# SCH_IMU_Tester_2024-10-07.net
KiCad netlist of a schematic drawn in EasyEDA
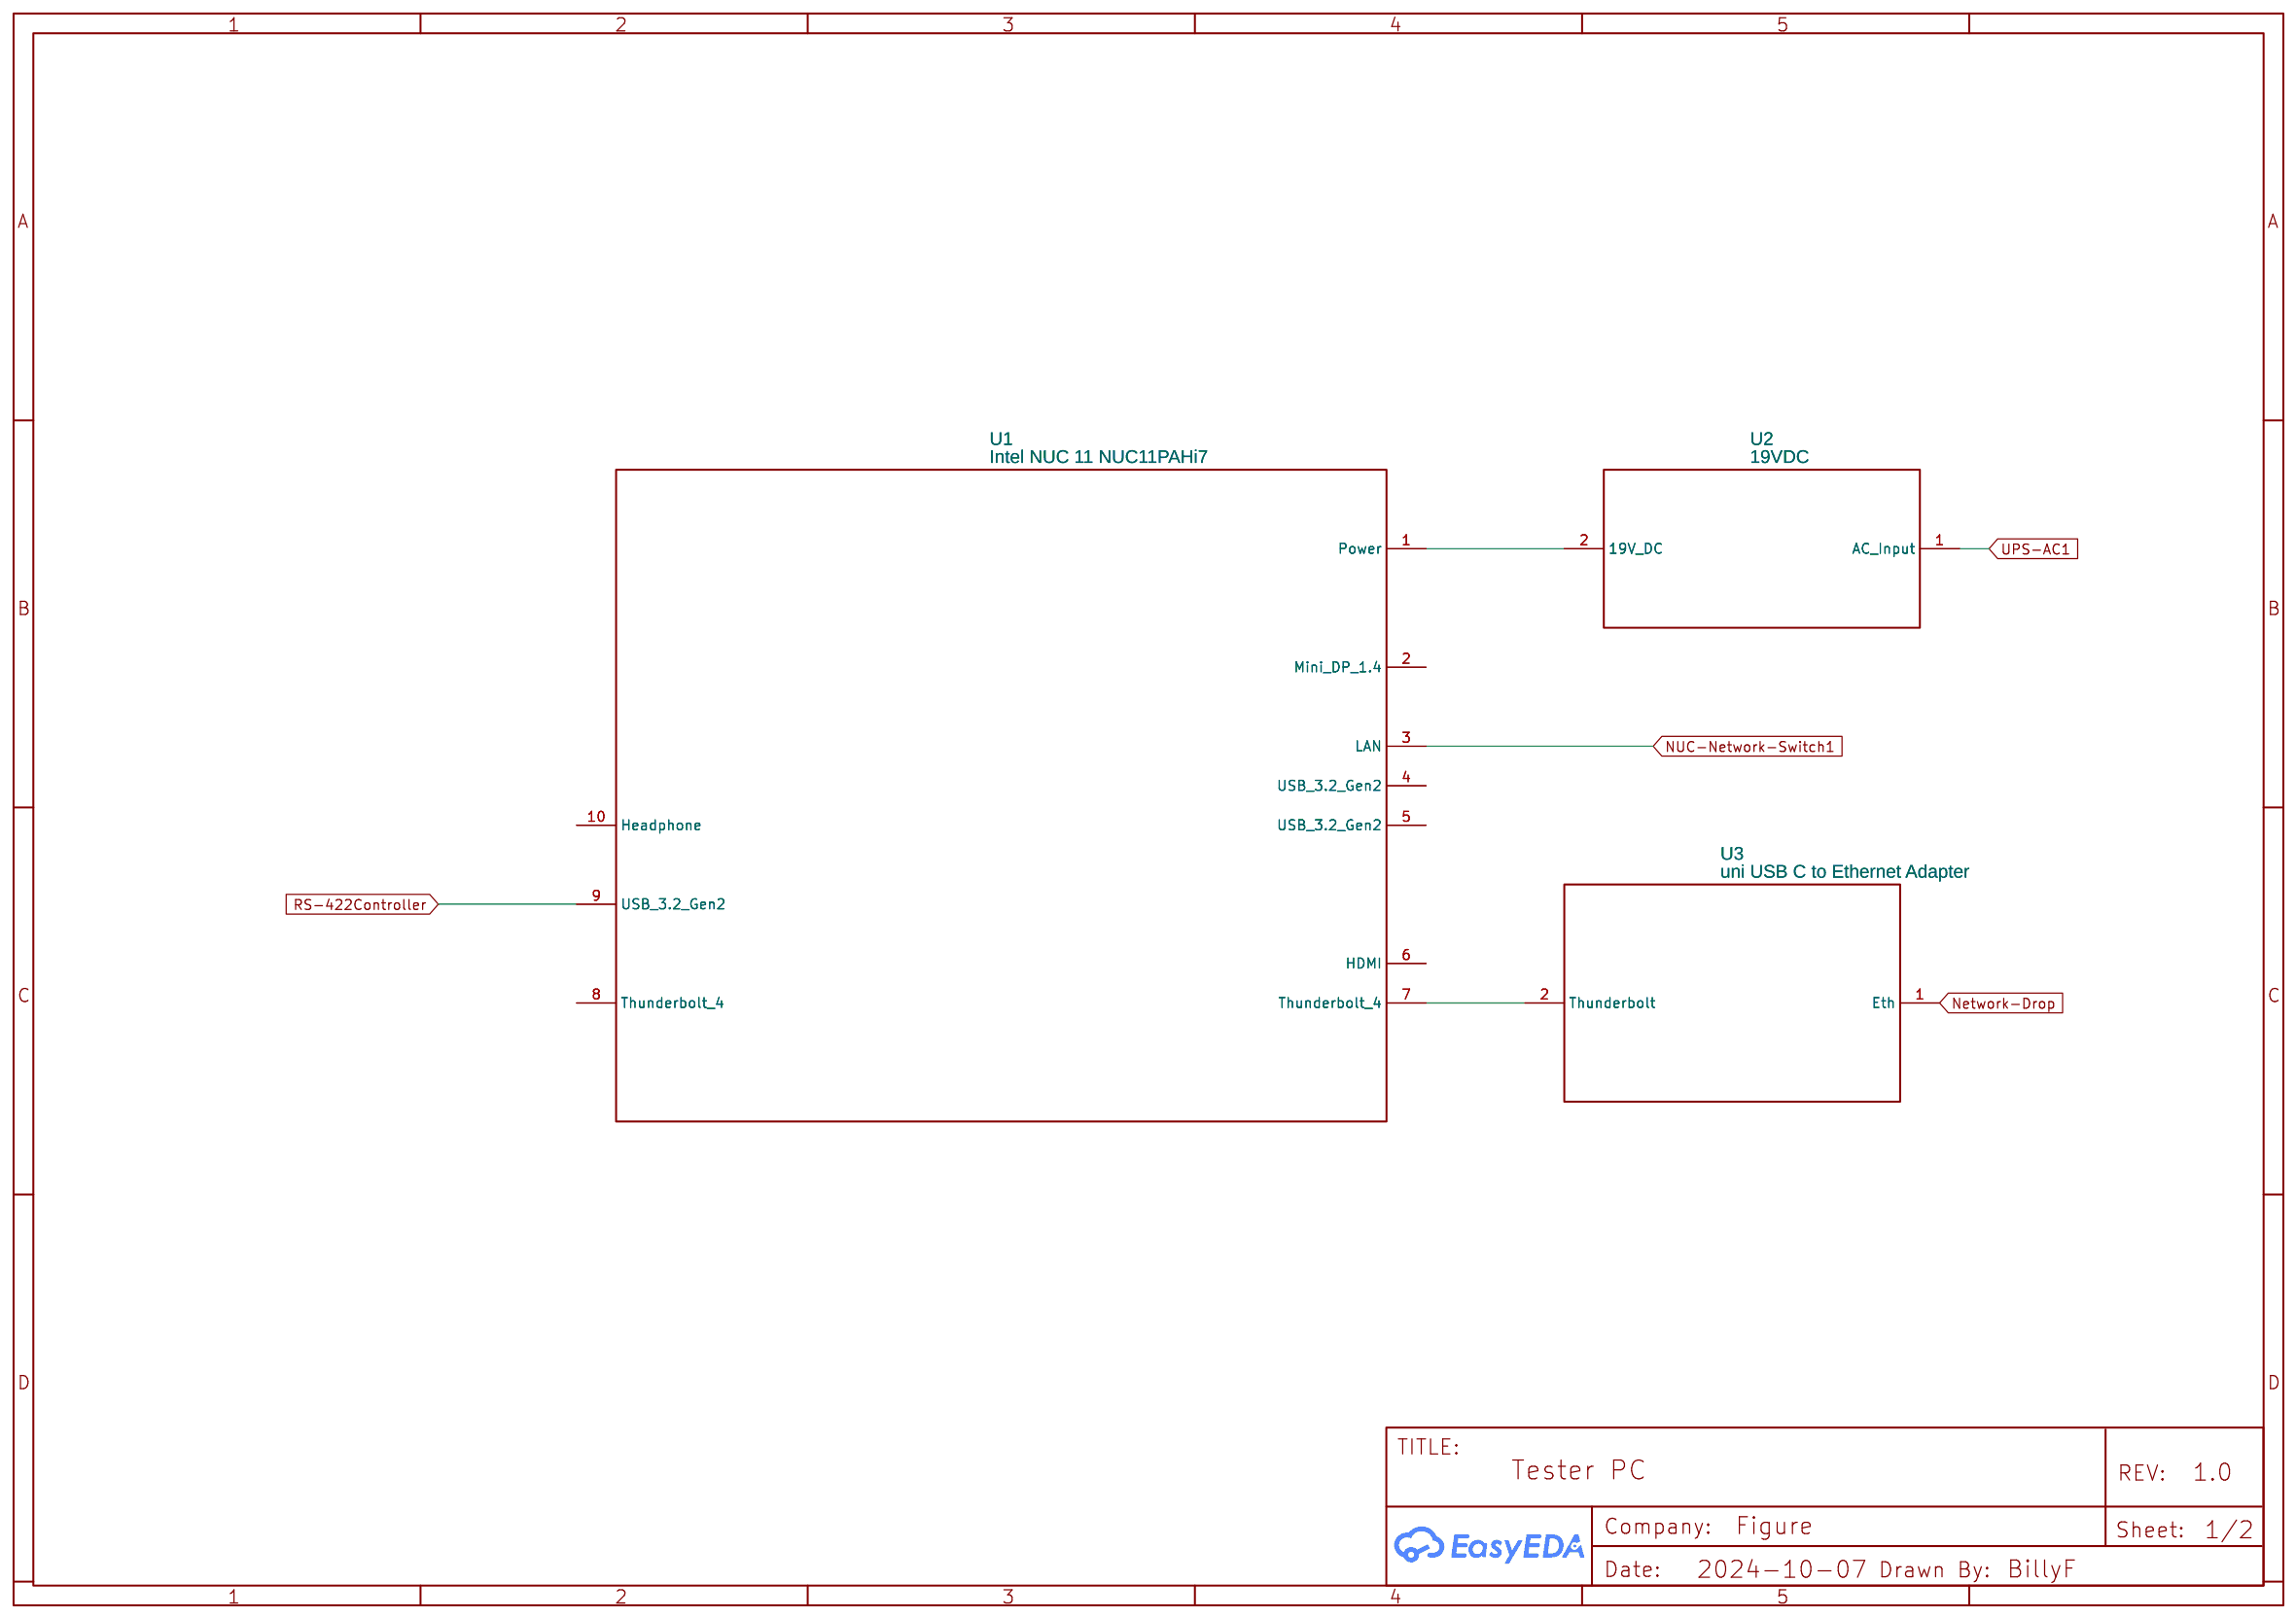
[diagram p0: Sheet_1]
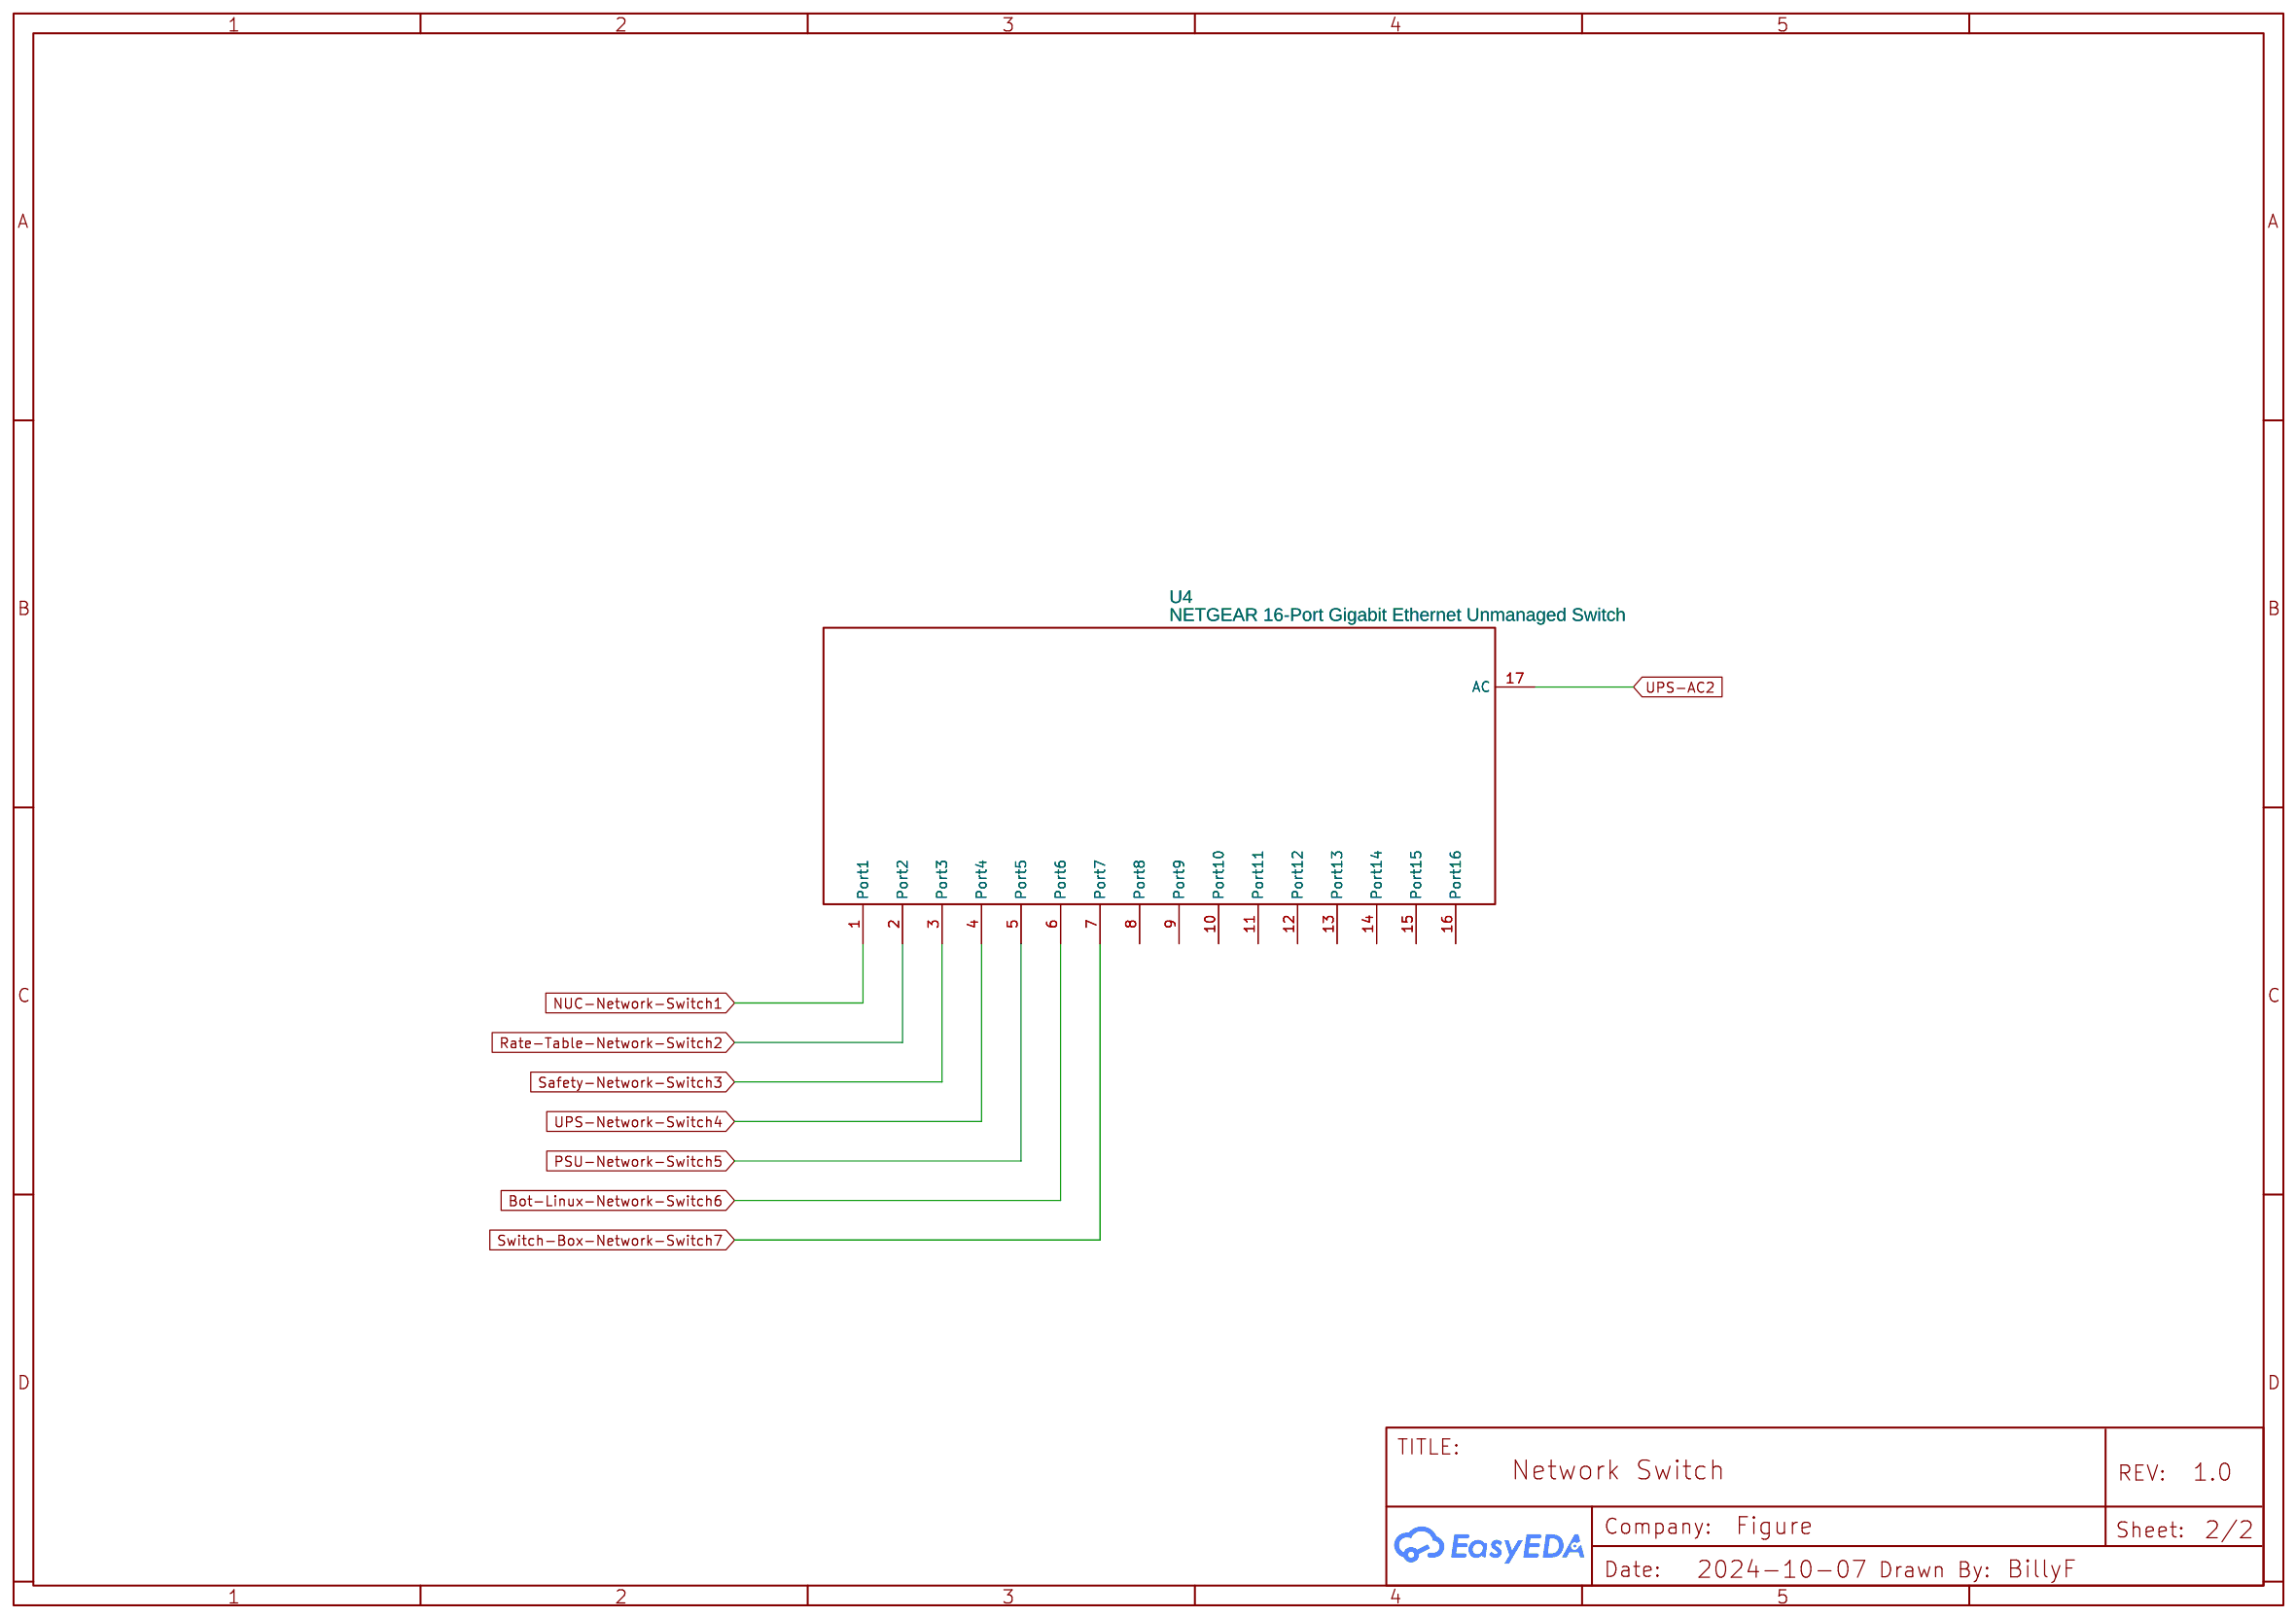
[diagram p1: Sheet_2]

(export (version "E")
  (design (tool "Eeschema 10.0.6"))
  (components
    (comp (ref "U1") (value "Intel NUC 11 NUC11PAHi7") (libsource (lib "") (part "Intel NUC 11 NUC11PAHi7")))
    (comp (ref "U2") (value "19VDC") (libsource (lib "") (part "19VDC")))
    (comp (ref "U3")
      (value "uni USB C to Ethernet Adapter")
      (libsource (lib "") (part "uni USB C to Ethernet Adapter"))
    )
    (comp (ref "U4")
      (value "NETGEAR 16-Port Gigabit Ethernet Unmanaged Switch")
      (fields (field (name "Manufacturer Part") "JGS516"))
      (libsource (lib "") (part "NETGEAR 16-Port Gigabit Ethernet Unmanaged Switch"))
    )
  )
  (nets
    (net (code "1") (name "Bot-Linux-Network-Switch6") (class "Default")
      (node (ref "U4") (pin "6") (pinfunction "Port6_6") (pintype "unspecified"))
    )
    (net (code "2") (name "NUC-Network-Switch1") (class "Default")
      (node (ref "U1") (pin "3") (pinfunction "LAN_3") (pintype "unspecified"))
      (node (ref "U4") (pin "1") (pinfunction "Port1_1") (pintype "unspecified"))
    )
    (net (code "3") (name "Net-(U1-Power)") (class "Default")
      (node (ref "U1") (pin "1") (pinfunction "Power_1") (pintype "unspecified"))
      (node (ref "U2") (pin "2") (pinfunction "19V_DC_2") (pintype "unspecified"))
    )
    (net (code "4") (name "Net-(U3-Thunderbolt)") (class "Default")
      (node (ref "U1") (pin "7") (pinfunction "Thunderbolt_4_7") (pintype "unspecified"))
      (node (ref "U3") (pin "2") (pinfunction "Thunderbolt_2") (pintype "unspecified"))
    )
    (net (code "5") (name "Network-Drop") (class "Default")
      (node (ref "U3") (pin "1") (pinfunction "Eth_1") (pintype "unspecified"))
    )
    (net (code "6") (name "PSU-Network-Switch5") (class "Default")
      (node (ref "U4") (pin "5") (pinfunction "Port5_5") (pintype "unspecified"))
    )
    (net (code "7") (name "RS-422Controller") (class "Default")
      (node (ref "U1") (pin "9") (pinfunction "USB_3.2_Gen2_9") (pintype "unspecified"))
    )
    (net (code "8") (name "Rate-Table-Network-Switch2") (class "Default")
      (node (ref "U4") (pin "2") (pinfunction "Port2_2") (pintype "unspecified"))
    )
    (net (code "9") (name "Safety-Network-Switch3") (class "Default")
      (node (ref "U4") (pin "3") (pinfunction "Port3_3") (pintype "unspecified"))
    )
    (net (code "10") (name "Switch-Box-Network-Switch7") (class "Default")
      (node (ref "U4") (pin "7") (pinfunction "Port7_7") (pintype "unspecified"))
    )
    (net (code "11") (name "UPS-AC1") (class "Default")
      (node (ref "U2") (pin "1") (pinfunction "AC_Input_1") (pintype "unspecified"))
    )
    (net (code "12") (name "UPS-AC2") (class "Default")
      (node (ref "U4") (pin "17") (pinfunction "AC_17") (pintype "unspecified"))
    )
    (net (code "13") (name "UPS-Network-Switch4") (class "Default")
      (node (ref "U4") (pin "4") (pinfunction "Port4_4") (pintype "unspecified"))
    )
    (net (code "14") (name "unconnected-(U1-HDMI-Pad6)") (class "Default")
      (node (ref "U1") (pin "6") (pinfunction "HDMI_6") (pintype "unspecified"))
    )
    (net (code "15") (name "unconnected-(U1-Headphone-Pad10)") (class "Default")
      (node (ref "U1") (pin "10") (pinfunction "Headphone_10") (pintype "unspecified"))
    )
    (net (code "16") (name "unconnected-(U1-Mini_DP_1.4-Pad2)") (class "Default")
      (node (ref "U1") (pin "2") (pinfunction "Mini_DP_1.4_2") (pintype "unspecified"))
    )
    (net (code "17") (name "unconnected-(U1-Thunderbolt_4-Pad8)") (class "Default")
      (node (ref "U1") (pin "8") (pinfunction "Thunderbolt_4_8") (pintype "unspecified"))
    )
    (net (code "18") (name "unconnected-(U1-USB_3.2_Gen2-Pad4)") (class "Default")
      (node (ref "U1") (pin "4") (pinfunction "USB_3.2_Gen2_4") (pintype "unspecified"))
    )
    (net (code "19") (name "unconnected-(U1-USB_3.2_Gen2-Pad5)") (class "Default")
      (node (ref "U1") (pin "5") (pinfunction "USB_3.2_Gen2_5") (pintype "unspecified"))
    )
    (net (code "20") (name "unconnected-(U4-Port8-Pad8)") (class "Default")
      (node (ref "U4") (pin "8") (pinfunction "Port8_8") (pintype "unspecified"))
    )
    (net (code "21") (name "unconnected-(U4-Port9-Pad9)") (class "Default")
      (node (ref "U4") (pin "9") (pinfunction "Port9_9") (pintype "unspecified"))
    )
    (net (code "22") (name "unconnected-(U4-Port10-Pad10)") (class "Default")
      (node (ref "U4") (pin "10") (pinfunction "Port10_10") (pintype "unspecified"))
    )
    (net (code "23") (name "unconnected-(U4-Port11-Pad11)") (class "Default")
      (node (ref "U4") (pin "11") (pinfunction "Port11_11") (pintype "unspecified"))
    )
    (net (code "24") (name "unconnected-(U4-Port12-Pad12)") (class "Default")
      (node (ref "U4") (pin "12") (pinfunction "Port12_12") (pintype "unspecified"))
    )
    (net (code "25") (name "unconnected-(U4-Port13-Pad13)") (class "Default")
      (node (ref "U4") (pin "13") (pinfunction "Port13_13") (pintype "unspecified"))
    )
    (net (code "26") (name "unconnected-(U4-Port14-Pad14)") (class "Default")
      (node (ref "U4") (pin "14") (pinfunction "Port14_14") (pintype "unspecified"))
    )
    (net (code "27") (name "unconnected-(U4-Port15-Pad15)") (class "Default")
      (node (ref "U4") (pin "15") (pinfunction "Port15_15") (pintype "unspecified"))
    )
    (net (code "28") (name "unconnected-(U4-Port16-Pad16)") (class "Default")
      (node (ref "U4") (pin "16") (pinfunction "Port16_16") (pintype "unspecified"))
    )
  )
)
